# placa2caras_CTO2_2.net
KiCad netlist of a schematic drawn in EAGLE
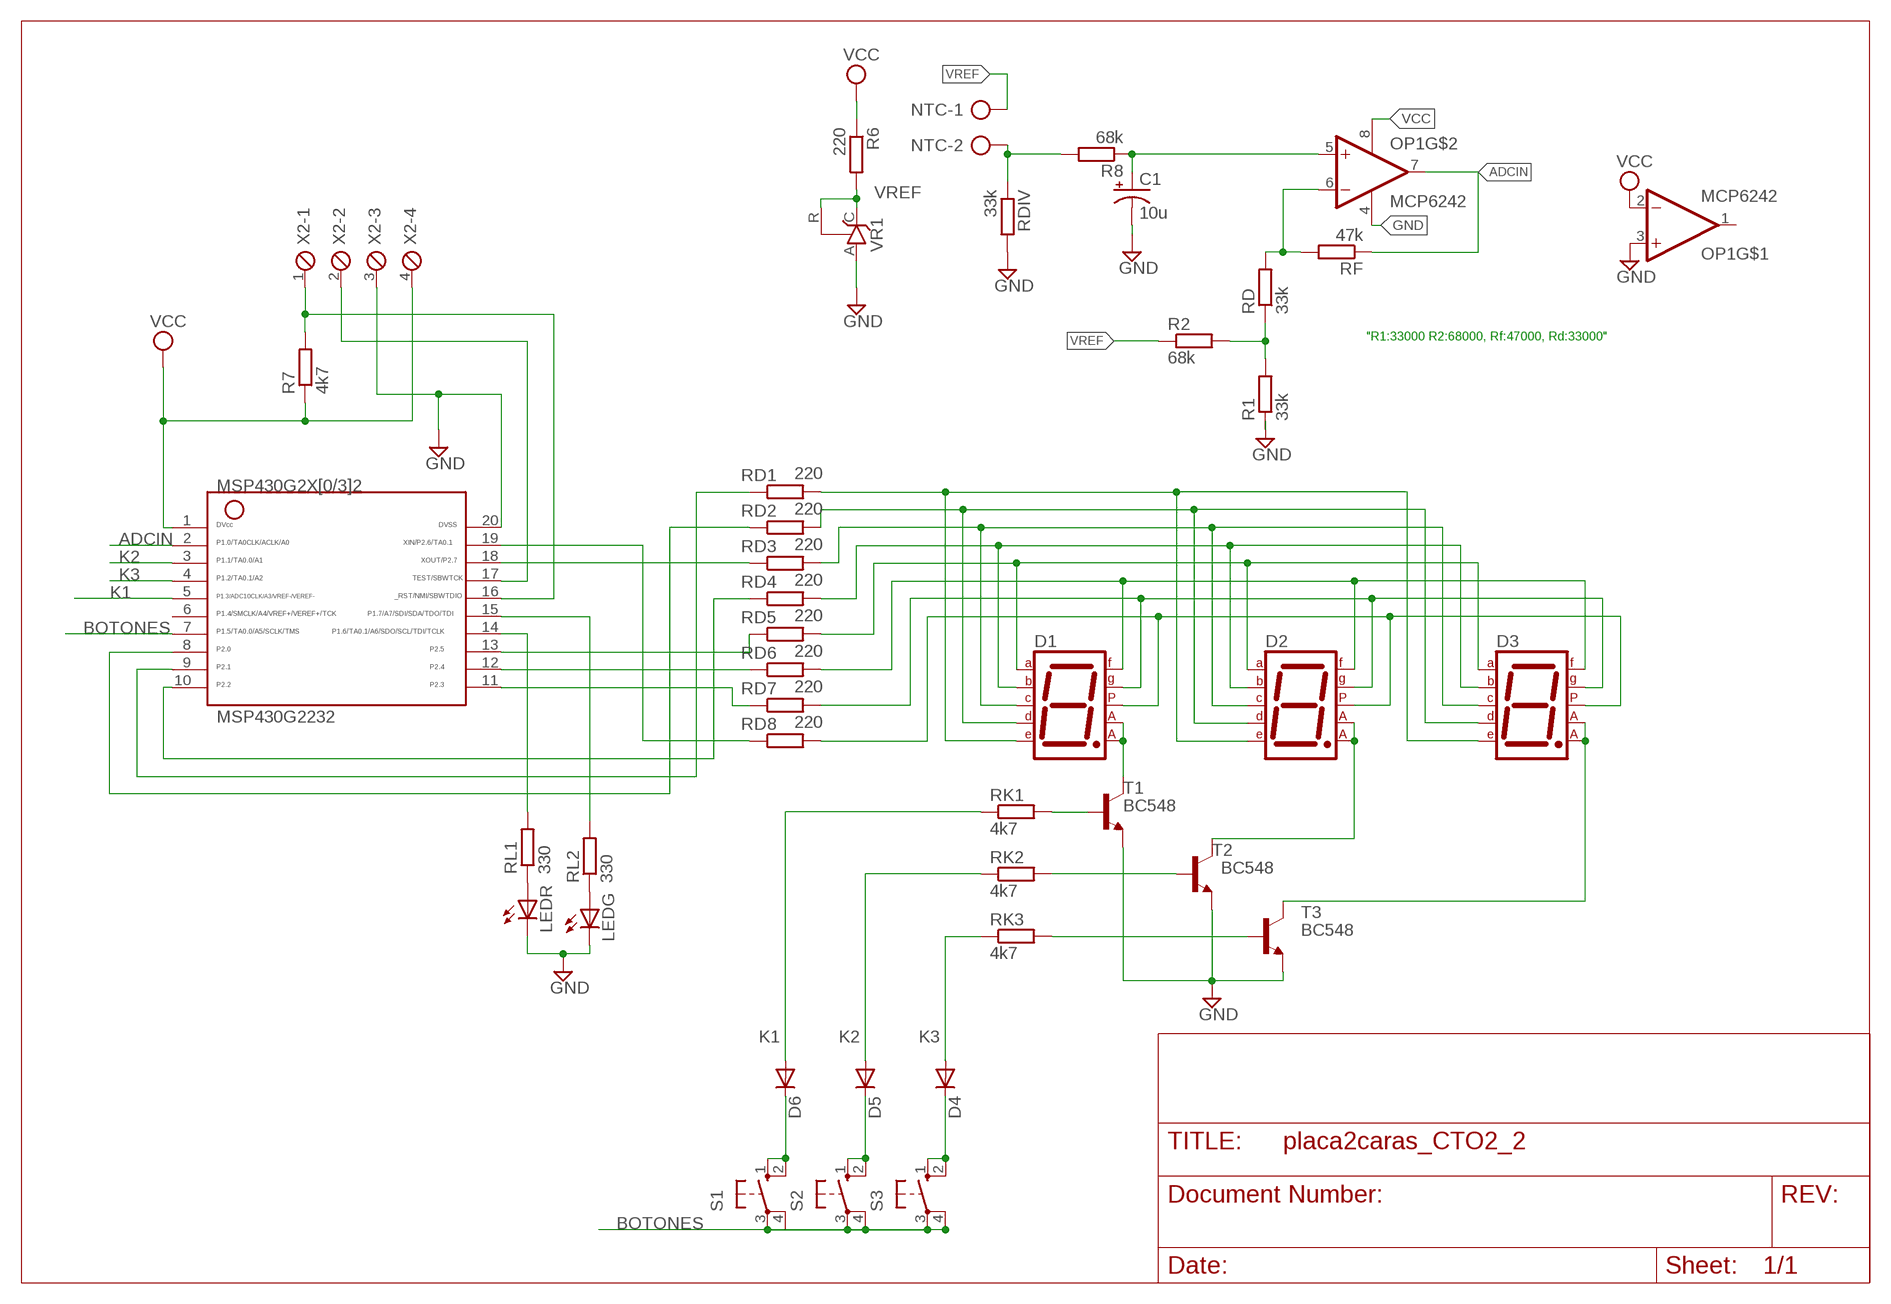
[diagram p0: schematic, sheet 1]

(export (version "E")
  (design (tool "Eeschema 10.0.6"))
  (components
    (comp (ref "C1")
      (value "10u")
      (footprint "eagle-import:E2,5-6E")
      (libsource (lib "eagle-import") (part "CPOL-USE2,5-6E"))
    )
    (comp (ref "D1")
      (value "7SEG-CA")
      (footprint "eagle-import:7SEG-13")
      (libsource (lib "eagle-import") (part "7SEG-CA"))
    )
    (comp (ref "D2")
      (value "7SEG-CA")
      (footprint "eagle-import:7SEG-13")
      (libsource (lib "eagle-import") (part "7SEG-CA"))
    )
    (comp (ref "D3")
      (value "7SEG-CA")
      (footprint "eagle-import:7SEG-13")
      (libsource (lib "eagle-import") (part "7SEG-CA"))
    )
    (comp (ref "D4")
      (value "1N4148DO35-10")
      (footprint "eagle-import:DO35-10")
      (libsource (lib "eagle-import") (part "1N4148DO35-10"))
    )
    (comp (ref "D5")
      (value "1N4148DO35-10")
      (footprint "eagle-import:DO35-10")
      (libsource (lib "eagle-import") (part "1N4148DO35-10"))
    )
    (comp (ref "D6")
      (value "1N4148DO35-10")
      (footprint "eagle-import:DO35-10")
      (libsource (lib "eagle-import") (part "1N4148DO35-10"))
    )
    (comp (ref "LEDG")
      (value "LED5MM")
      (footprint "eagle-import:LED5MM")
      (libsource (lib "eagle-import") (part "LED5MM"))
    )
    (comp (ref "LEDR")
      (value "LED5MM")
      (footprint "eagle-import:LED5MM")
      (libsource (lib "eagle-import") (part "LED5MM"))
    )
    (comp (ref "MSP430G2232")
      (value "G2X[0/3]2---N20")
      (footprint "eagle-import:N20")
      (libsource (lib "eagle-import") (part "G2X[0/3]2---N20"))
    )
    (comp (ref "NTC")
      (value "AK500/2")
      (footprint "eagle-import:AK500_2")
      (libsource (lib "eagle-import") (part "AK500/2"))
    )
    (comp (ref "OP1")
      (value "MCP6242")
      (footprint "eagle-import:DIL8_MOD")
      (libsource (lib "eagle-import") (part "MCP6242CONPADGORDO"))
    )
    (comp (ref "R1")
      (value "33k")
      (footprint "eagle-import:0207_10")
      (libsource (lib "eagle-import") (part "resistor_mod2_R-EU_0207/10"))
    )
    (comp (ref "R2")
      (value "68k")
      (footprint "eagle-import:0207_10")
      (libsource (lib "eagle-import") (part "resistor_mod2_R-EU_0207/10"))
    )
    (comp (ref "R6")
      (value "220")
      (footprint "eagle-import:0207_10")
      (libsource (lib "eagle-import") (part "resistor_mod2_R-EU_0207/10"))
    )
    (comp (ref "R7")
      (value "4k7")
      (footprint "eagle-import:0207_10")
      (libsource (lib "eagle-import") (part "resistor_mod2_R-EU_0207/10"))
    )
    (comp (ref "R8")
      (value "68k")
      (footprint "eagle-import:0207_10")
      (libsource (lib "eagle-import") (part "resistor_mod2_R-EU_0207/10"))
    )
    (comp (ref "RD")
      (value "33k")
      (footprint "eagle-import:0207_10")
      (libsource (lib "eagle-import") (part "resistor_mod2_R-EU_0207/10"))
    )
    (comp (ref "RD1")
      (value "220")
      (footprint "eagle-import:0207_10")
      (libsource (lib "eagle-import") (part "resistor_mod2_R-EU_0207/10"))
    )
    (comp (ref "RD2")
      (value "220")
      (footprint "eagle-import:0207_10")
      (libsource (lib "eagle-import") (part "resistor_mod2_R-EU_0207/10"))
    )
    (comp (ref "RD3")
      (value "220")
      (footprint "eagle-import:0207_10")
      (libsource (lib "eagle-import") (part "resistor_mod2_R-EU_0207/10"))
    )
    (comp (ref "RD4")
      (value "220")
      (footprint "eagle-import:0207_10")
      (libsource (lib "eagle-import") (part "resistor_mod2_R-EU_0207/10"))
    )
    (comp (ref "RD5")
      (value "220")
      (footprint "eagle-import:0207_10")
      (libsource (lib "eagle-import") (part "resistor_mod2_R-EU_0207/10"))
    )
    (comp (ref "RD6")
      (value "220")
      (footprint "eagle-import:0207_10")
      (libsource (lib "eagle-import") (part "resistor_mod2_R-EU_0207/10"))
    )
    (comp (ref "RD7")
      (value "220")
      (footprint "eagle-import:0207_10")
      (libsource (lib "eagle-import") (part "resistor_mod2_R-EU_0207/10"))
    )
    (comp (ref "RD8")
      (value "220")
      (footprint "eagle-import:0207_10")
      (libsource (lib "eagle-import") (part "resistor_mod2_R-EU_0207/10"))
    )
    (comp (ref "RDIV")
      (value "33k")
      (footprint "eagle-import:0207_10")
      (libsource (lib "eagle-import") (part "resistor_mod2_R-EU_0207/10"))
    )
    (comp (ref "RF")
      (value "47k")
      (footprint "eagle-import:0207_10")
      (libsource (lib "eagle-import") (part "resistor_mod2_R-EU_0207/10"))
    )
    (comp (ref "RK1")
      (value "4k7")
      (footprint "eagle-import:0207_10")
      (libsource (lib "eagle-import") (part "resistor_mod2_R-EU_0207/10"))
    )
    (comp (ref "RK2")
      (value "4k7")
      (footprint "eagle-import:0207_10")
      (libsource (lib "eagle-import") (part "resistor_mod2_R-EU_0207/10"))
    )
    (comp (ref "RK3")
      (value "4k7")
      (footprint "eagle-import:0207_10")
      (libsource (lib "eagle-import") (part "resistor_mod2_R-EU_0207/10"))
    )
    (comp (ref "RL1")
      (value "330")
      (footprint "eagle-import:0207_10")
      (libsource (lib "eagle-import") (part "R-EU_0207/10"))
    )
    (comp (ref "RL2")
      (value "330")
      (footprint "eagle-import:0207_10")
      (libsource (lib "eagle-import") (part "R-EU_0207/10"))
    )
    (comp (ref "S1")
      (value "10-XX")
      (footprint "eagle-import:B3F-10XX")
      (fields (field (name "MPN") "B3F-1000"))
      (libsource (lib "eagle-import") (part "10-XX"))
    )
    (comp (ref "S2")
      (value "10-XX")
      (footprint "eagle-import:B3F-10XX")
      (fields (field (name "MPN") "B3F-1000"))
      (libsource (lib "eagle-import") (part "10-XX"))
    )
    (comp (ref "S3")
      (value "10-XX")
      (footprint "eagle-import:B3F-10XX")
      (fields (field (name "MPN") "B3F-1000"))
      (libsource (lib "eagle-import") (part "10-XX"))
    )
    (comp (ref "T1")
      (value "BC548")
      (footprint "eagle-import:TO92-EBC")
      (libsource (lib "eagle-import") (part "BC548"))
    )
    (comp (ref "T2")
      (value "BC548")
      (footprint "eagle-import:TO92-EBC")
      (libsource (lib "eagle-import") (part "BC548"))
    )
    (comp (ref "T3")
      (value "BC548")
      (footprint "eagle-import:TO92-EBC")
      (libsource (lib "eagle-import") (part "BC548"))
    )
    (comp (ref "VR1")
      (value "TL431CLP")
      (footprint "eagle-import:TO92-CLP")
      (libsource (lib "eagle-import") (part "TL431CLP"))
    )
    (comp (ref "X2")
      (value "MPT4")
      (footprint "eagle-import:4POL254")
      (libsource (lib "eagle-import") (part "MPT4"))
    )
  )
  (nets
    (net (code "1") (name "/BOTONES") (class "Default")
      (node (ref "MSP430G2232") (pin "7") (pinfunction "7_7") (pintype "bidirectional"))
      (node (ref "S1") (pin "3") (pinfunction "P_3") (pintype "passive"))
      (node (ref "S1") (pin "4") (pinfunction "P1_4") (pintype "passive"))
      (node (ref "S2") (pin "3") (pinfunction "P_3") (pintype "passive"))
      (node (ref "S2") (pin "4") (pinfunction "P1_4") (pintype "passive"))
      (node (ref "S3") (pin "3") (pinfunction "P_3") (pintype "passive"))
      (node (ref "S3") (pin "4") (pinfunction "P1_4") (pintype "passive"))
    )
    (net (code "2") (name "/K1") (class "Default")
      (node (ref "D6") (pin "A") (pinfunction "A_A") (pintype "passive"))
      (node (ref "MSP430G2232") (pin "5") (pinfunction "5_5") (pintype "bidirectional"))
      (node (ref "RK1") (pin "1") (pinfunction "1_1") (pintype "passive"))
    )
    (net (code "3") (name "/K2") (class "Default")
      (node (ref "D5") (pin "A") (pinfunction "A_A") (pintype "passive"))
      (node (ref "MSP430G2232") (pin "3") (pinfunction "3_3") (pintype "bidirectional"))
      (node (ref "RK2") (pin "1") (pinfunction "1_1") (pintype "passive"))
    )
    (net (code "4") (name "/K3") (class "Default")
      (node (ref "D4") (pin "A") (pinfunction "A_A") (pintype "passive"))
      (node (ref "MSP430G2232") (pin "4") (pinfunction "4_4") (pintype "bidirectional"))
      (node (ref "RK3") (pin "1") (pinfunction "1_1") (pintype "passive"))
    )
    (net (code "5") (name "ADCIN") (class "Default")
      (node (ref "MSP430G2232") (pin "2") (pinfunction "2_2") (pintype "bidirectional"))
      (node (ref "OP1") (pin "7") (pinfunction "OUT_7") (pintype "output"))
      (node (ref "RF") (pin "1") (pinfunction "1_1") (pintype "passive"))
    )
    (net (code "6") (name "GND") (class "Default")
      (node (ref "C1") (pin "-") (pinfunction "-_-") (pintype "passive"))
      (node (ref "LEDG") (pin "K") (pinfunction "C_K") (pintype "passive"))
      (node (ref "LEDR") (pin "K") (pinfunction "C_K") (pintype "passive"))
      (node (ref "MSP430G2232") (pin "20") (pinfunction "20_20") (pintype "bidirectional"))
      (node (ref "OP1") (pin "3") (pinfunction "+IN_3") (pintype "input"))
      (node (ref "OP1") (pin "4") (pinfunction "V-_4") (pintype "power_in"))
      (node (ref "R1") (pin "1") (pinfunction "1_1") (pintype "passive"))
      (node (ref "RDIV") (pin "2") (pinfunction "2_2") (pintype "passive"))
      (node (ref "T1") (pin "E") (pinfunction "E_E") (pintype "passive"))
      (node (ref "T2") (pin "E") (pinfunction "E_E") (pintype "passive"))
      (node (ref "T3") (pin "E") (pinfunction "E_E") (pintype "passive"))
      (node (ref "VR1") (pin "A") (pinfunction "A_A") (pintype "passive"))
      (node (ref "X2") (pin "3") (pinfunction "1_3") (pintype "passive"))
    )
    (net (code "7") (name "Net-(D1-A)") (class "Default")
      (node (ref "D1") (pin "7") (pinfunction "A_7") (pintype "passive"))
      (node (ref "D2") (pin "7") (pinfunction "A_7") (pintype "passive"))
      (node (ref "D3") (pin "7") (pinfunction "A_7") (pintype "passive"))
      (node (ref "RD5") (pin "2") (pinfunction "2_2") (pintype "passive"))
    )
    (net (code "8") (name "Net-(D1-B)") (class "Default")
      (node (ref "D1") (pin "6") (pinfunction "B_6") (pintype "passive"))
      (node (ref "D2") (pin "6") (pinfunction "B_6") (pintype "passive"))
      (node (ref "D3") (pin "6") (pinfunction "B_6") (pintype "passive"))
      (node (ref "RD4") (pin "2") (pinfunction "2_2") (pintype "passive"))
    )
    (net (code "9") (name "Net-(D1-C)") (class "Default")
      (node (ref "D1") (pin "4") (pinfunction "C_4") (pintype "passive"))
      (node (ref "D2") (pin "4") (pinfunction "C_4") (pintype "passive"))
      (node (ref "D3") (pin "4") (pinfunction "C_4") (pintype "passive"))
      (node (ref "RD3") (pin "2") (pinfunction "2_2") (pintype "passive"))
    )
    (net (code "10") (name "Net-(D1-CA1)") (class "Default")
      (node (ref "D1") (pin "3") (pinfunction "CA1_3") (pintype "passive"))
      (node (ref "D1") (pin "8") (pinfunction "CA2_8") (pintype "passive"))
      (node (ref "T1") (pin "C") (pinfunction "C_C") (pintype "passive"))
    )
    (net (code "11") (name "Net-(D1-D)") (class "Default")
      (node (ref "D1") (pin "2") (pinfunction "D_2") (pintype "passive"))
      (node (ref "D2") (pin "2") (pinfunction "D_2") (pintype "passive"))
      (node (ref "D3") (pin "2") (pinfunction "D_2") (pintype "passive"))
      (node (ref "RD2") (pin "2") (pinfunction "2_2") (pintype "passive"))
    )
    (net (code "12") (name "Net-(D1-DP)") (class "Default")
      (node (ref "D1") (pin "5") (pinfunction "DP_5") (pintype "passive"))
      (node (ref "D2") (pin "5") (pinfunction "DP_5") (pintype "passive"))
      (node (ref "D3") (pin "5") (pinfunction "DP_5") (pintype "passive"))
      (node (ref "RD8") (pin "2") (pinfunction "2_2") (pintype "passive"))
    )
    (net (code "13") (name "Net-(D1-E)") (class "Default")
      (node (ref "D1") (pin "1") (pinfunction "E_1") (pintype "passive"))
      (node (ref "D2") (pin "1") (pinfunction "E_1") (pintype "passive"))
      (node (ref "D3") (pin "1") (pinfunction "E_1") (pintype "passive"))
      (node (ref "RD1") (pin "2") (pinfunction "2_2") (pintype "passive"))
    )
    (net (code "14") (name "Net-(D1-F)") (class "Default")
      (node (ref "D1") (pin "9") (pinfunction "F_9") (pintype "passive"))
      (node (ref "D2") (pin "9") (pinfunction "F_9") (pintype "passive"))
      (node (ref "D3") (pin "9") (pinfunction "F_9") (pintype "passive"))
      (node (ref "RD6") (pin "2") (pinfunction "2_2") (pintype "passive"))
    )
    (net (code "15") (name "Net-(D1-G)") (class "Default")
      (node (ref "D1") (pin "10") (pinfunction "G_10") (pintype "passive"))
      (node (ref "D2") (pin "10") (pinfunction "G_10") (pintype "passive"))
      (node (ref "D3") (pin "10") (pinfunction "G_10") (pintype "passive"))
      (node (ref "RD7") (pin "2") (pinfunction "2_2") (pintype "passive"))
    )
    (net (code "16") (name "Net-(D2-CA1)") (class "Default")
      (node (ref "D2") (pin "3") (pinfunction "CA1_3") (pintype "passive"))
      (node (ref "D2") (pin "8") (pinfunction "CA2_8") (pintype "passive"))
      (node (ref "T2") (pin "C") (pinfunction "C_C") (pintype "passive"))
    )
    (net (code "17") (name "Net-(D3-CA1)") (class "Default")
      (node (ref "D3") (pin "3") (pinfunction "CA1_3") (pintype "passive"))
      (node (ref "D3") (pin "8") (pinfunction "CA2_8") (pintype "passive"))
      (node (ref "T3") (pin "C") (pinfunction "C_C") (pintype "passive"))
    )
    (net (code "18") (name "Net-(LEDG-PadA)") (class "Default")
      (node (ref "LEDG") (pin "A") (pinfunction "A_A") (pintype "passive"))
      (node (ref "RL2") (pin "1") (pinfunction "1_1") (pintype "passive"))
    )
    (net (code "19") (name "Net-(LEDR-PadA)") (class "Default")
      (node (ref "LEDR") (pin "A") (pinfunction "A_A") (pintype "passive"))
      (node (ref "RL1") (pin "1") (pinfunction "1_1") (pintype "passive"))
    )
    (net (code "20") (name "Net-(MSP430G2232-Pad8)") (class "Default")
      (node (ref "MSP430G2232") (pin "8") (pinfunction "8_8") (pintype "bidirectional"))
      (node (ref "RD2") (pin "1") (pinfunction "1_1") (pintype "passive"))
    )
    (net (code "21") (name "Net-(MSP430G2232-Pad9)") (class "Default")
      (node (ref "MSP430G2232") (pin "9") (pinfunction "9_9") (pintype "bidirectional"))
      (node (ref "RD1") (pin "1") (pinfunction "1_1") (pintype "passive"))
    )
    (net (code "22") (name "Net-(MSP430G2232-Pad10)") (class "Default")
      (node (ref "MSP430G2232") (pin "10") (pinfunction "10_10") (pintype "bidirectional"))
      (node (ref "RD4") (pin "1") (pinfunction "1_1") (pintype "passive"))
    )
    (net (code "23") (name "Net-(MSP430G2232-Pad11)") (class "Default")
      (node (ref "MSP430G2232") (pin "11") (pinfunction "11_11") (pintype "bidirectional"))
      (node (ref "RD7") (pin "1") (pinfunction "1_1") (pintype "passive"))
    )
    (net (code "24") (name "Net-(MSP430G2232-Pad12)") (class "Default")
      (node (ref "MSP430G2232") (pin "12") (pinfunction "12_12") (pintype "bidirectional"))
      (node (ref "RD6") (pin "1") (pinfunction "1_1") (pintype "passive"))
    )
    (net (code "25") (name "Net-(MSP430G2232-Pad13)") (class "Default")
      (node (ref "MSP430G2232") (pin "13") (pinfunction "13_13") (pintype "bidirectional"))
      (node (ref "RD5") (pin "1") (pinfunction "1_1") (pintype "passive"))
    )
    (net (code "26") (name "Net-(MSP430G2232-Pad14)") (class "Default")
      (node (ref "MSP430G2232") (pin "14") (pinfunction "14_14") (pintype "bidirectional"))
      (node (ref "RL1") (pin "2") (pinfunction "2_2") (pintype "passive"))
    )
    (net (code "27") (name "Net-(MSP430G2232-Pad15)") (class "Default")
      (node (ref "MSP430G2232") (pin "15") (pinfunction "15_15") (pintype "bidirectional"))
      (node (ref "RL2") (pin "2") (pinfunction "2_2") (pintype "passive"))
    )
    (net (code "28") (name "Net-(MSP430G2232-Pad16)") (class "Default")
      (node (ref "MSP430G2232") (pin "16") (pinfunction "16_16") (pintype "bidirectional"))
      (node (ref "R7") (pin "2") (pinfunction "2_2") (pintype "passive"))
      (node (ref "X2") (pin "1") (pinfunction "1_1") (pintype "passive"))
    )
    (net (code "29") (name "Net-(MSP430G2232-Pad18)") (class "Default")
      (node (ref "MSP430G2232") (pin "18") (pinfunction "18_18") (pintype "bidirectional"))
      (node (ref "RD3") (pin "1") (pinfunction "1_1") (pintype "passive"))
    )
    (net (code "30") (name "Net-(MSP430G2232-Pad19)") (class "Default")
      (node (ref "MSP430G2232") (pin "19") (pinfunction "19_19") (pintype "bidirectional"))
      (node (ref "RD8") (pin "1") (pinfunction "1_1") (pintype "passive"))
    )
    (net (code "31") (name "Net-(NTCB-KL)") (class "Default")
      (node (ref "NTC") (pin "2") (pinfunction "KL_2") (pintype "passive"))
      (node (ref "R8") (pin "2") (pinfunction "2_2") (pintype "passive"))
      (node (ref "RDIV") (pin "1") (pinfunction "1_1") (pintype "passive"))
    )
    (net (code "32") (name "Net-(OP1B-+IN)") (class "Default")
      (node (ref "C1") (pin "+") (pinfunction "+_+") (pintype "passive"))
      (node (ref "OP1") (pin "5") (pinfunction "+IN_5") (pintype "input"))
      (node (ref "R8") (pin "1") (pinfunction "1_1") (pintype "passive"))
    )
    (net (code "33") (name "Net-(OP1B--IN)") (class "Default")
      (node (ref "OP1") (pin "6") (pinfunction "-IN_6") (pintype "input"))
      (node (ref "RD") (pin "2") (pinfunction "2_2") (pintype "passive"))
      (node (ref "RF") (pin "2") (pinfunction "2_2") (pintype "passive"))
    )
    (net (code "34") (name "Net-(R1-Pad2)") (class "Default")
      (node (ref "R1") (pin "2") (pinfunction "2_2") (pintype "passive"))
      (node (ref "R2") (pin "2") (pinfunction "2_2") (pintype "passive"))
      (node (ref "RD") (pin "1") (pinfunction "1_1") (pintype "passive"))
    )
    (net (code "35") (name "Net-(RK1-Pad2)") (class "Default")
      (node (ref "RK1") (pin "2") (pinfunction "2_2") (pintype "passive"))
      (node (ref "T1") (pin "B") (pinfunction "B_B") (pintype "passive"))
    )
    (net (code "36") (name "Net-(RK2-Pad2)") (class "Default")
      (node (ref "RK2") (pin "2") (pinfunction "2_2") (pintype "passive"))
      (node (ref "T2") (pin "B") (pinfunction "B_B") (pintype "passive"))
    )
    (net (code "37") (name "Net-(RK3-Pad2)") (class "Default")
      (node (ref "RK3") (pin "2") (pinfunction "2_2") (pintype "passive"))
      (node (ref "T3") (pin "B") (pinfunction "B_B") (pintype "passive"))
    )
    (net (code "38") (name "Net-(S1-S)") (class "Default")
      (node (ref "D6") (pin "C") (pinfunction "C_C") (pintype "passive"))
      (node (ref "S1") (pin "1") (pinfunction "S_1") (pintype "passive"))
      (node (ref "S1") (pin "2") (pinfunction "S1_2") (pintype "passive"))
    )
    (net (code "39") (name "Net-(S2-S)") (class "Default")
      (node (ref "D5") (pin "C") (pinfunction "C_C") (pintype "passive"))
      (node (ref "S2") (pin "1") (pinfunction "S_1") (pintype "passive"))
      (node (ref "S2") (pin "2") (pinfunction "S1_2") (pintype "passive"))
    )
    (net (code "40") (name "Net-(S3-S)") (class "Default")
      (node (ref "D4") (pin "C") (pinfunction "C_C") (pintype "passive"))
      (node (ref "S3") (pin "1") (pinfunction "S_1") (pintype "passive"))
      (node (ref "S3") (pin "2") (pinfunction "S1_2") (pintype "passive"))
    )
    (net (code "41") (name "Net-(X2B-1)") (class "Default")
      (node (ref "MSP430G2232") (pin "17") (pinfunction "17_17") (pintype "bidirectional"))
      (node (ref "X2") (pin "2") (pinfunction "1_2") (pintype "passive"))
    )
    (net (code "42") (name "VCC") (class "Default")
      (node (ref "MSP430G2232") (pin "1") (pinfunction "1_1") (pintype "bidirectional"))
      (node (ref "OP1") (pin "2") (pinfunction "-IN_2") (pintype "input"))
      (node (ref "OP1") (pin "8") (pinfunction "V+_8") (pintype "power_in"))
      (node (ref "R6") (pin "1") (pinfunction "1_1") (pintype "passive"))
      (node (ref "R7") (pin "1") (pinfunction "1_1") (pintype "passive"))
      (node (ref "X2") (pin "4") (pinfunction "1_4") (pintype "passive"))
    )
    (net (code "43") (name "VREF") (class "Default")
      (node (ref "NTC") (pin "1") (pinfunction "KL_1") (pintype "passive"))
      (node (ref "R2") (pin "1") (pinfunction "1_1") (pintype "passive"))
      (node (ref "R6") (pin "2") (pinfunction "2_2") (pintype "passive"))
      (node (ref "VR1") (pin "C") (pinfunction "C_C") (pintype "passive"))
      (node (ref "VR1") (pin "R") (pinfunction "R_R") (pintype "passive"))
    )
    (net (code "44") (name "unconnected-(MSP430G2232-Pad6)") (class "Default")
      (node (ref "MSP430G2232") (pin "6") (pinfunction "6_6") (pintype "bidirectional"))
    )
    (net (code "45") (name "unconnected-(OP1A-OUT-Pad1)") (class "Default")
      (node (ref "OP1") (pin "1") (pinfunction "OUT_1") (pintype "output"))
    )
  )
)
